# 13448_ATMEGA328_prog.net
KiCad netlist of a schematic drawn in EAGLE
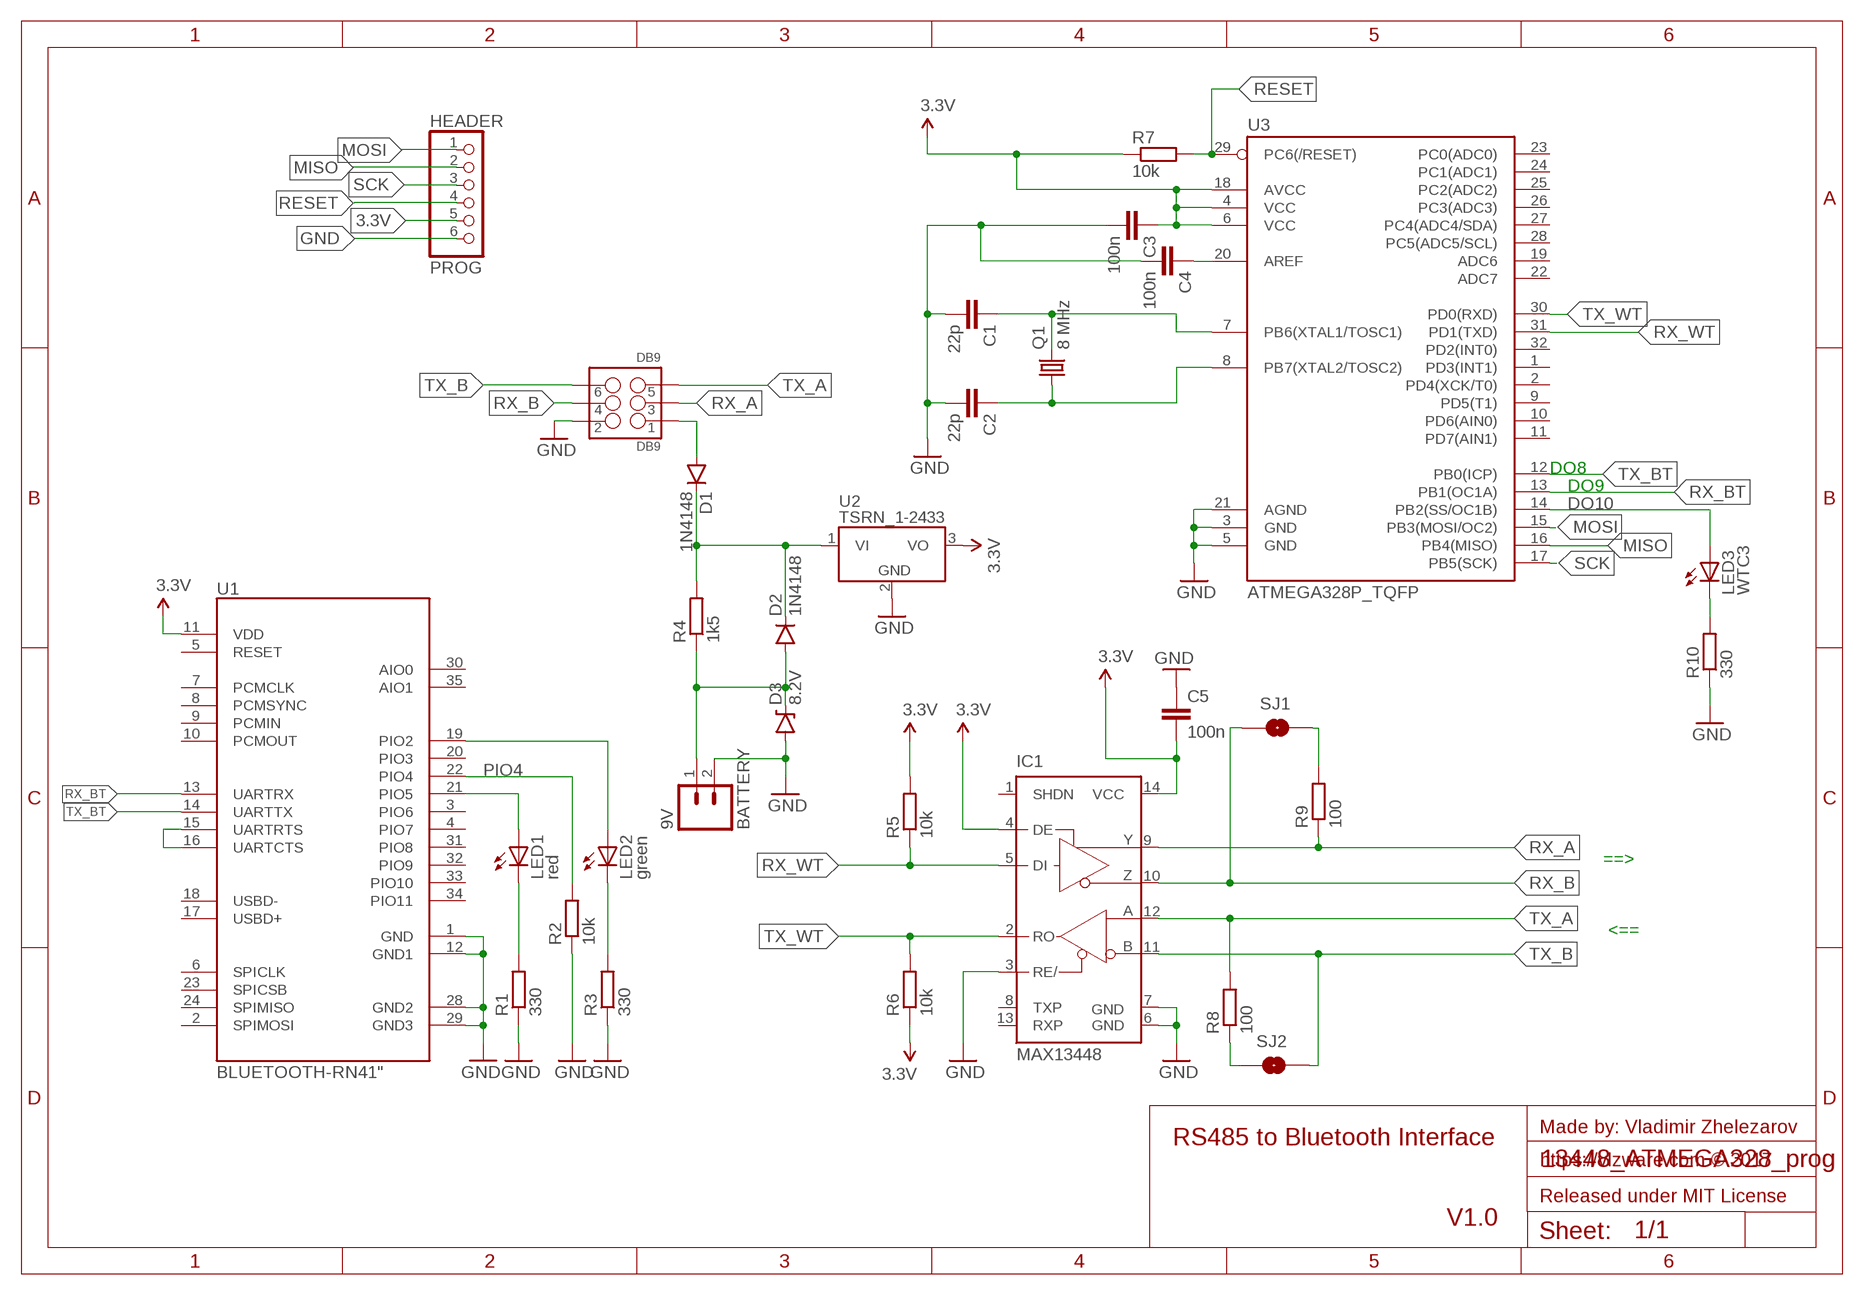
[diagram p0: schematic, sheet 1]

(export (version "E")
  (design (tool "Eeschema 10.0.6"))
  (components
    (comp (ref "BATTERY")
      (value "9V")
      (footprint "eagle-import:1X02_LOCK")
      (libsource (lib "eagle-import") (part "M02LOCK"))
    )
    (comp (ref "C1")
      (value "22p")
      (footprint "eagle-import:1206")
      (libsource (lib "eagle-import") (part "CAP1206"))
    )
    (comp (ref "C2")
      (value "22p")
      (footprint "eagle-import:1206")
      (libsource (lib "eagle-import") (part "CAP1206"))
    )
    (comp (ref "C3")
      (value "100n")
      (footprint "eagle-import:1206")
      (libsource (lib "eagle-import") (part "CAP1206"))
    )
    (comp (ref "C4")
      (value "100n")
      (footprint "eagle-import:1206")
      (libsource (lib "eagle-import") (part "CAP1206"))
    )
    (comp (ref "C5")
      (value "100n")
      (footprint "eagle-import:1206")
      (libsource (lib "eagle-import") (part "CAP1206"))
    )
    (comp (ref "D1")
      (value "1N4148")
      (footprint "eagle-import:DIODE-1N4148")
      (libsource (lib "eagle-import") (part "DIODE1N4148"))
    )
    (comp (ref "D2")
      (value "1N4148")
      (footprint "eagle-import:DIODE-1N4148")
      (libsource (lib "eagle-import") (part "DIODE1N4148"))
    )
    (comp (ref "D3")
      (value "8.2V")
      (footprint "eagle-import:DIODE-BZT52")
      (libsource (lib "eagle-import") (part "DIODE-ZENER"))
    )
    (comp (ref "DB9")
      (value "DB9")
      (footprint "eagle-import:2X3")
      (libsource (lib "eagle-import") (part "M03X22X3_SILK_MALE_PTH"))
    )
    (comp (ref "HEADER")
      (value "PROG")
      (footprint "eagle-import:1X06")
      (libsource (lib "eagle-import") (part "PINHD-1X6"))
    )
    (comp (ref "IC1")
      (value "MAX13448")
      (footprint "eagle-import:SO14")
      (fields (field (name "MPN") "MAX3465CSD+"))
      (libsource (lib "eagle-import") (part "MAX346SD5C"))
    )
    (comp (ref "LED1")
      (value "red")
      (footprint "eagle-import:LED3MM")
      (libsource (lib "eagle-import") (part "LED3MM"))
    )
    (comp (ref "LED2")
      (value "green")
      (footprint "eagle-import:LED3MM")
      (libsource (lib "eagle-import") (part "LED3MM"))
    )
    (comp (ref "LED3")
      (value "WTC3")
      (footprint "eagle-import:LED3MM")
      (libsource (lib "eagle-import") (part "LED3MM"))
    )
    (comp (ref "Q1")
      (value "8 MHz")
      (footprint "eagle-import:HC49UP")
      (libsource (lib "eagle-import") (part "CRYSTALHC49UP"))
    )
    (comp (ref "R1")
      (value "330")
      (footprint "eagle-import:M1206")
      (libsource (lib "eagle-import") (part "R-EU_M1206"))
    )
    (comp (ref "R2")
      (value "10k")
      (footprint "eagle-import:M1206")
      (libsource (lib "eagle-import") (part "R-EU_M1206"))
    )
    (comp (ref "R3")
      (value "330")
      (footprint "eagle-import:M1206")
      (libsource (lib "eagle-import") (part "R-EU_M1206"))
    )
    (comp (ref "R4")
      (value "1k5")
      (footprint "eagle-import:0204V")
      (libsource (lib "eagle-import") (part "R-EU_0204/2V"))
    )
    (comp (ref "R5")
      (value "10k")
      (footprint "eagle-import:M1206")
      (libsource (lib "eagle-import") (part "R-EU_M1206"))
    )
    (comp (ref "R6")
      (value "10k")
      (footprint "eagle-import:M1206")
      (libsource (lib "eagle-import") (part "R-EU_M1206"))
    )
    (comp (ref "R7")
      (value "10k")
      (footprint "eagle-import:M1206")
      (libsource (lib "eagle-import") (part "R-EU_M1206"))
    )
    (comp (ref "R8")
      (value "100")
      (footprint "eagle-import:M1206")
      (libsource (lib "eagle-import") (part "R-EU_M1206"))
    )
    (comp (ref "R9")
      (value "100")
      (footprint "eagle-import:M1206")
      (libsource (lib "eagle-import") (part "R-EU_M1206"))
    )
    (comp (ref "R10")
      (value "330")
      (footprint "eagle-import:M1206")
      (libsource (lib "eagle-import") (part "R-EU_M1206"))
    )
    (comp (ref "SJ1")
      (value "SOLDERJUMPERNC")
      (footprint "eagle-import:SJ_2S")
      (libsource (lib "eagle-import") (part "SOLDERJUMPERNC"))
    )
    (comp (ref "SJ2")
      (value "SOLDERJUMPERNC")
      (footprint "eagle-import:SJ_2S")
      (libsource (lib "eagle-import") (part "SOLDERJUMPERNC"))
    )
    (comp (ref "U1")
      (value "BLUETOOTH-RN41\"")
      (footprint "eagle-import:RN41")
      (libsource (lib "eagle-import") (part "BLUETOOTH-RN41{dblquote}"))
    )
    (comp (ref "U2")
      (value "TSRN_1-2433")
      (footprint "eagle-import:TSR-1")
      (libsource (lib "eagle-import") (part "TSR_1-2450"))
    )
    (comp (ref "U3")
      (value "ATMEGA328P_TQFP")
      (footprint "eagle-import:TQFP32-08")
      (libsource (lib "eagle-import") (part "ATMEGA328P_TQFP"))
    )
  )
  (nets
    (net (code "1") (name "/DO10") (class "Default")
      (node (ref "LED3") (pin "A") (pinfunction "A_A") (pintype "passive"))
      (node (ref "U3") (pin "14") (pinfunction "PB2(SS/OC1B)_14") (pintype "bidirectional"))
    )
    (net (code "2") (name "/PIO4") (class "Default")
      (node (ref "R2") (pin "2") (pinfunction "2_2") (pintype "passive"))
      (node (ref "U1") (pin "22") (pinfunction "PIO4_22") (pintype "bidirectional"))
    )
    (net (code "3") (name "3.3V") (class "Default")
      (node (ref "C3") (pin "1") (pinfunction "1_1") (pintype "passive"))
      (node (ref "C5") (pin "2") (pinfunction "2_2") (pintype "passive"))
      (node (ref "HEADER") (pin "5") (pinfunction "5_5") (pintype "passive"))
      (node (ref "IC1") (pin "14") (pinfunction "VCC_14") (pintype "power_in"))
      (node (ref "IC1") (pin "4") (pinfunction "DE_4") (pintype "input"))
      (node (ref "R5") (pin "2") (pinfunction "2_2") (pintype "passive"))
      (node (ref "R6") (pin "1") (pinfunction "1_1") (pintype "passive"))
      (node (ref "R7") (pin "1") (pinfunction "1_1") (pintype "passive"))
      (node (ref "U1") (pin "11") (pinfunction "VDD_11") (pintype "bidirectional"))
      (node (ref "U2") (pin "3") (pinfunction "VO_3") (pintype "power_in"))
      (node (ref "U3") (pin "18") (pinfunction "AVCC_18") (pintype "bidirectional"))
      (node (ref "U3") (pin "4") (pinfunction "VCC_4") (pintype "bidirectional"))
      (node (ref "U3") (pin "6") (pinfunction "VCC_6") (pintype "bidirectional"))
    )
    (net (code "4") (name "GND") (class "Default")
      (node (ref "BATTERY") (pin "2") (pinfunction "2_2") (pintype "passive"))
      (node (ref "C1") (pin "2") (pinfunction "2_2") (pintype "passive"))
      (node (ref "C2") (pin "2") (pinfunction "2_2") (pintype "passive"))
      (node (ref "C3") (pin "2") (pinfunction "2_2") (pintype "passive"))
      (node (ref "C4") (pin "2") (pinfunction "2_2") (pintype "passive"))
      (node (ref "C5") (pin "1") (pinfunction "1_1") (pintype "passive"))
      (node (ref "D3") (pin "A") (pinfunction "A_A") (pintype "passive"))
      (node (ref "DB9") (pin "2") (pinfunction "2_2") (pintype "bidirectional"))
      (node (ref "HEADER") (pin "6") (pinfunction "6_6") (pintype "passive"))
      (node (ref "IC1") (pin "3") (pinfunction "RE/_3") (pintype "input"))
      (node (ref "IC1") (pin "6") (pinfunction "GND_6") (pintype "power_in"))
      (node (ref "IC1") (pin "7") (pinfunction "GND_7") (pintype "power_in"))
      (node (ref "R1") (pin "1") (pinfunction "1_1") (pintype "passive"))
      (node (ref "R10") (pin "1") (pinfunction "1_1") (pintype "passive"))
      (node (ref "R2") (pin "1") (pinfunction "1_1") (pintype "passive"))
      (node (ref "R3") (pin "1") (pinfunction "1_1") (pintype "passive"))
      (node (ref "U1") (pin "1") (pinfunction "GND_1") (pintype "bidirectional"))
      (node (ref "U1") (pin "12") (pinfunction "GND1_12") (pintype "bidirectional"))
      (node (ref "U1") (pin "28") (pinfunction "GND2_28") (pintype "bidirectional"))
      (node (ref "U1") (pin "29") (pinfunction "GND3_29") (pintype "bidirectional"))
      (node (ref "U2") (pin "2") (pinfunction "GND_2") (pintype "power_in"))
      (node (ref "U3") (pin "21") (pinfunction "AGND_21") (pintype "bidirectional"))
      (node (ref "U3") (pin "3") (pinfunction "GND_3") (pintype "bidirectional"))
      (node (ref "U3") (pin "5") (pinfunction "GND_5") (pintype "bidirectional"))
    )
    (net (code "5") (name "MISO") (class "Default")
      (node (ref "HEADER") (pin "2") (pinfunction "2_2") (pintype "passive"))
      (node (ref "U3") (pin "16") (pinfunction "PB4(MISO)_16") (pintype "bidirectional"))
    )
    (net (code "6") (name "MOSI") (class "Default")
      (node (ref "HEADER") (pin "1") (pinfunction "1_1") (pintype "passive"))
      (node (ref "U3") (pin "15") (pinfunction "PB3(MOSI/OC2)_15") (pintype "bidirectional"))
    )
    (net (code "7") (name "Net-(BATTERY-Pad1)") (class "Default")
      (node (ref "BATTERY") (pin "1") (pinfunction "1_1") (pintype "passive"))
      (node (ref "D2") (pin "A") (pinfunction "A_A") (pintype "passive"))
      (node (ref "D3") (pin "C") (pinfunction "C_C") (pintype "passive"))
      (node (ref "R4") (pin "1") (pinfunction "1_1") (pintype "passive"))
    )
    (net (code "8") (name "Net-(D1-PadA)") (class "Default")
      (node (ref "D1") (pin "A") (pinfunction "A_A") (pintype "passive"))
      (node (ref "DB9") (pin "1") (pinfunction "1_1") (pintype "bidirectional"))
    )
    (net (code "9") (name "Net-(LED1-C)") (class "Default")
      (node (ref "LED1") (pin "K") (pinfunction "C_K") (pintype "passive"))
      (node (ref "R1") (pin "2") (pinfunction "2_2") (pintype "passive"))
    )
    (net (code "10") (name "Net-(LED2-C)") (class "Default")
      (node (ref "LED2") (pin "K") (pinfunction "C_K") (pintype "passive"))
      (node (ref "R3") (pin "2") (pinfunction "2_2") (pintype "passive"))
    )
    (net (code "11") (name "Net-(LED3-C)") (class "Default")
      (node (ref "LED3") (pin "K") (pinfunction "C_K") (pintype "passive"))
      (node (ref "R10") (pin "2") (pinfunction "2_2") (pintype "passive"))
    )
    (net (code "12") (name "Net-(R8-Pad1)") (class "Default")
      (node (ref "R8") (pin "1") (pinfunction "1_1") (pintype "passive"))
      (node (ref "SJ2") (pin "1") (pinfunction "1_1") (pintype "passive"))
    )
    (net (code "13") (name "Net-(R9-Pad2)") (class "Default")
      (node (ref "R9") (pin "2") (pinfunction "2_2") (pintype "passive"))
      (node (ref "SJ1") (pin "2") (pinfunction "2_2") (pintype "passive"))
    )
    (net (code "14") (name "Net-(U1-PIO2)") (class "Default")
      (node (ref "LED2") (pin "A") (pinfunction "A_A") (pintype "passive"))
      (node (ref "U1") (pin "19") (pinfunction "PIO2_19") (pintype "bidirectional"))
    )
    (net (code "15") (name "Net-(U1-PIO5)") (class "Default")
      (node (ref "LED1") (pin "A") (pinfunction "A_A") (pintype "passive"))
      (node (ref "U1") (pin "21") (pinfunction "PIO5_21") (pintype "bidirectional"))
    )
    (net (code "16") (name "Net-(U1-UARTCTS)") (class "Default")
      (node (ref "U1") (pin "15") (pinfunction "UARTRTS_15") (pintype "bidirectional"))
      (node (ref "U1") (pin "16") (pinfunction "UARTCTS_16") (pintype "bidirectional"))
    )
    (net (code "17") (name "Net-(U2-VI)") (class "Default")
      (node (ref "D1") (pin "C") (pinfunction "C_C") (pintype "passive"))
      (node (ref "D2") (pin "C") (pinfunction "C_C") (pintype "passive"))
      (node (ref "R4") (pin "2") (pinfunction "2_2") (pintype "passive"))
      (node (ref "U2") (pin "1") (pinfunction "VI_1") (pintype "power_in"))
    )
    (net (code "18") (name "Net-(U3-AREF)") (class "Default")
      (node (ref "C4") (pin "1") (pinfunction "1_1") (pintype "passive"))
      (node (ref "U3") (pin "20") (pinfunction "AREF_20") (pintype "bidirectional"))
    )
    (net (code "19") (name "Net-(U3-PB6(XTAL1{slash}TOSC1))") (class "Default")
      (node (ref "C1") (pin "1") (pinfunction "1_1") (pintype "passive"))
      (node (ref "Q1") (pin "2") (pinfunction "2_2") (pintype "passive"))
      (node (ref "U3") (pin "7") (pinfunction "PB6(XTAL1/TOSC1)_7") (pintype "bidirectional"))
    )
    (net (code "20") (name "Net-(U3-PB7(XTAL2{slash}TOSC2))") (class "Default")
      (node (ref "C2") (pin "1") (pinfunction "1_1") (pintype "passive"))
      (node (ref "Q1") (pin "1") (pinfunction "1_1") (pintype "passive"))
      (node (ref "U3") (pin "8") (pinfunction "PB7(XTAL2/TOSC2)_8") (pintype "bidirectional"))
    )
    (net (code "21") (name "RESET") (class "Default")
      (node (ref "HEADER") (pin "4") (pinfunction "4_4") (pintype "passive"))
      (node (ref "R7") (pin "2") (pinfunction "2_2") (pintype "passive"))
      (node (ref "U3") (pin "29") (pinfunction "PC6(/RESET)_29") (pintype "bidirectional"))
    )
    (net (code "22") (name "RX_A") (class "Default")
      (node (ref "DB9") (pin "3") (pinfunction "3_3") (pintype "bidirectional"))
      (node (ref "IC1") (pin "9") (pinfunction "Y_9") (pintype "output"))
      (node (ref "R9") (pin "1") (pinfunction "1_1") (pintype "passive"))
    )
    (net (code "23") (name "RX_B") (class "Default")
      (node (ref "DB9") (pin "4") (pinfunction "4_4") (pintype "bidirectional"))
      (node (ref "IC1") (pin "10") (pinfunction "Z_10") (pintype "output"))
      (node (ref "SJ1") (pin "1") (pinfunction "1_1") (pintype "passive"))
    )
    (net (code "24") (name "RX_BT") (class "Default")
      (node (ref "U1") (pin "13") (pinfunction "UARTRX_13") (pintype "bidirectional"))
      (node (ref "U3") (pin "13") (pinfunction "PB1(OC1A)_13") (pintype "bidirectional"))
    )
    (net (code "25") (name "RX_WT") (class "Default")
      (node (ref "IC1") (pin "5") (pinfunction "DI_5") (pintype "input"))
      (node (ref "R5") (pin "1") (pinfunction "1_1") (pintype "passive"))
      (node (ref "U3") (pin "31") (pinfunction "PD1(TXD)_31") (pintype "bidirectional"))
    )
    (net (code "26") (name "SCK") (class "Default")
      (node (ref "HEADER") (pin "3") (pinfunction "3_3") (pintype "passive"))
      (node (ref "U3") (pin "17") (pinfunction "PB5(SCK)_17") (pintype "bidirectional"))
    )
    (net (code "27") (name "TX_A") (class "Default")
      (node (ref "DB9") (pin "5") (pinfunction "5_5") (pintype "bidirectional"))
      (node (ref "IC1") (pin "12") (pinfunction "A_12") (pintype "input"))
      (node (ref "R8") (pin "2") (pinfunction "2_2") (pintype "passive"))
    )
    (net (code "28") (name "TX_B") (class "Default")
      (node (ref "DB9") (pin "6") (pinfunction "6_6") (pintype "bidirectional"))
      (node (ref "IC1") (pin "11") (pinfunction "B_11") (pintype "input"))
      (node (ref "SJ2") (pin "2") (pinfunction "2_2") (pintype "passive"))
    )
    (net (code "29") (name "TX_BT") (class "Default")
      (node (ref "U1") (pin "14") (pinfunction "UARTTX_14") (pintype "bidirectional"))
      (node (ref "U3") (pin "12") (pinfunction "PB0(ICP)_12") (pintype "bidirectional"))
    )
    (net (code "30") (name "TX_WT") (class "Default")
      (node (ref "IC1") (pin "2") (pinfunction "RO_2") (pintype "output"))
      (node (ref "R6") (pin "2") (pinfunction "2_2") (pintype "passive"))
      (node (ref "U3") (pin "30") (pinfunction "PD0(RXD)_30") (pintype "bidirectional"))
    )
    (net (code "31") (name "unconnected-(IC1-RXP-Pad13)") (class "Default")
      (node (ref "IC1") (pin "13") (pinfunction "RXP_13") (pintype "passive"))
    )
    (net (code "32") (name "unconnected-(IC1-SHDN-Pad1)") (class "Default")
      (node (ref "IC1") (pin "1") (pinfunction "SHDN_1") (pintype "input"))
    )
    (net (code "33") (name "unconnected-(IC1-TXP-Pad8)") (class "Default")
      (node (ref "IC1") (pin "8") (pinfunction "TXP_8") (pintype "passive"))
    )
    (net (code "34") (name "unconnected-(U1-AIO0-Pad30)") (class "Default")
      (node (ref "U1") (pin "30") (pinfunction "AIO0_30") (pintype "bidirectional"))
    )
    (net (code "35") (name "unconnected-(U1-AIO1-Pad35)") (class "Default")
      (node (ref "U1") (pin "35") (pinfunction "AIO1_35") (pintype "bidirectional"))
    )
    (net (code "36") (name "unconnected-(U1-PCMCLK-Pad7)") (class "Default")
      (node (ref "U1") (pin "7") (pinfunction "PCMCLK_7") (pintype "bidirectional"))
    )
    (net (code "37") (name "unconnected-(U1-PCMIN-Pad9)") (class "Default")
      (node (ref "U1") (pin "9") (pinfunction "PCMIN_9") (pintype "bidirectional"))
    )
    (net (code "38") (name "unconnected-(U1-PCMOUT-Pad10)") (class "Default")
      (node (ref "U1") (pin "10") (pinfunction "PCMOUT_10") (pintype "bidirectional"))
    )
    (net (code "39") (name "unconnected-(U1-PCMSYNC-Pad8)") (class "Default")
      (node (ref "U1") (pin "8") (pinfunction "PCMSYNC_8") (pintype "bidirectional"))
    )
    (net (code "40") (name "unconnected-(U1-PIO3-Pad20)") (class "Default")
      (node (ref "U1") (pin "20") (pinfunction "PIO3_20") (pintype "bidirectional"))
    )
    (net (code "41") (name "unconnected-(U1-PIO6-Pad3)") (class "Default")
      (node (ref "U1") (pin "3") (pinfunction "PIO6_3") (pintype "bidirectional"))
    )
    (net (code "42") (name "unconnected-(U1-PIO7-Pad4)") (class "Default")
      (node (ref "U1") (pin "4") (pinfunction "PIO7_4") (pintype "bidirectional"))
    )
    (net (code "43") (name "unconnected-(U1-PIO8-Pad31)") (class "Default")
      (node (ref "U1") (pin "31") (pinfunction "PIO8_31") (pintype "bidirectional"))
    )
    (net (code "44") (name "unconnected-(U1-PIO9-Pad32)") (class "Default")
      (node (ref "U1") (pin "32") (pinfunction "PIO9_32") (pintype "bidirectional"))
    )
    (net (code "45") (name "unconnected-(U1-PIO10-Pad33)") (class "Default")
      (node (ref "U1") (pin "33") (pinfunction "PIO10_33") (pintype "bidirectional"))
    )
    (net (code "46") (name "unconnected-(U1-PIO11-Pad34)") (class "Default")
      (node (ref "U1") (pin "34") (pinfunction "PIO11_34") (pintype "bidirectional"))
    )
    (net (code "47") (name "unconnected-(U1-RESET-Pad5)") (class "Default")
      (node (ref "U1") (pin "5") (pinfunction "RESET_5") (pintype "bidirectional"))
    )
    (net (code "48") (name "unconnected-(U1-SPICLK-Pad6)") (class "Default")
      (node (ref "U1") (pin "6") (pinfunction "SPICLK_6") (pintype "bidirectional"))
    )
    (net (code "49") (name "unconnected-(U1-SPICSB-Pad23)") (class "Default")
      (node (ref "U1") (pin "23") (pinfunction "SPICSB_23") (pintype "bidirectional"))
    )
    (net (code "50") (name "unconnected-(U1-SPIMISO-Pad24)") (class "Default")
      (node (ref "U1") (pin "24") (pinfunction "SPIMISO_24") (pintype "bidirectional"))
    )
    (net (code "51") (name "unconnected-(U1-SPIMOSI-Pad2)") (class "Default")
      (node (ref "U1") (pin "2") (pinfunction "SPIMOSI_2") (pintype "bidirectional"))
    )
    (net (code "52") (name "unconnected-(U1-USBD+-Pad17)") (class "Default")
      (node (ref "U1") (pin "17") (pinfunction "USBD+_17") (pintype "bidirectional"))
    )
    (net (code "53") (name "unconnected-(U1-USBD--Pad18)") (class "Default")
      (node (ref "U1") (pin "18") (pinfunction "USBD-_18") (pintype "bidirectional"))
    )
    (net (code "54") (name "unconnected-(U3-ADC6-Pad19)") (class "Default")
      (node (ref "U3") (pin "19") (pinfunction "ADC6_19") (pintype "bidirectional"))
    )
    (net (code "55") (name "unconnected-(U3-ADC7-Pad22)") (class "Default")
      (node (ref "U3") (pin "22") (pinfunction "ADC7_22") (pintype "bidirectional"))
    )
    (net (code "56") (name "unconnected-(U3-PC0(ADC0)-Pad23)") (class "Default")
      (node (ref "U3") (pin "23") (pinfunction "PC0(ADC0)_23") (pintype "bidirectional"))
    )
    (net (code "57") (name "unconnected-(U3-PC1(ADC1)-Pad24)") (class "Default")
      (node (ref "U3") (pin "24") (pinfunction "PC1(ADC1)_24") (pintype "bidirectional"))
    )
    (net (code "58") (name "unconnected-(U3-PC2(ADC2)-Pad25)") (class "Default")
      (node (ref "U3") (pin "25") (pinfunction "PC2(ADC2)_25") (pintype "bidirectional"))
    )
    (net (code "59") (name "unconnected-(U3-PC3(ADC3)-Pad26)") (class "Default")
      (node (ref "U3") (pin "26") (pinfunction "PC3(ADC3)_26") (pintype "bidirectional"))
    )
    (net (code "60") (name "unconnected-(U3-PC4(ADC4{slash}SDA)-Pad27)") (class "Default")
      (node (ref "U3") (pin "27") (pinfunction "PC4(ADC4/SDA)_27") (pintype "bidirectional"))
    )
    (net (code "61") (name "unconnected-(U3-PC5(ADC5{slash}SCL)-Pad28)") (class "Default")
      (node (ref "U3") (pin "28") (pinfunction "PC5(ADC5/SCL)_28") (pintype "bidirectional"))
    )
    (net (code "62") (name "unconnected-(U3-PD2(INT0)-Pad32)") (class "Default")
      (node (ref "U3") (pin "32") (pinfunction "PD2(INT0)_32") (pintype "bidirectional"))
    )
    (net (code "63") (name "unconnected-(U3-PD3(INT1)-Pad1)") (class "Default")
      (node (ref "U3") (pin "1") (pinfunction "PD3(INT1)_1") (pintype "bidirectional"))
    )
    (net (code "64") (name "unconnected-(U3-PD4(XCK{slash}T0)-Pad2)") (class "Default")
      (node (ref "U3") (pin "2") (pinfunction "PD4(XCK/T0)_2") (pintype "bidirectional"))
    )
    (net (code "65") (name "unconnected-(U3-PD5(T1)-Pad9)") (class "Default")
      (node (ref "U3") (pin "9") (pinfunction "PD5(T1)_9") (pintype "bidirectional"))
    )
    (net (code "66") (name "unconnected-(U3-PD6(AIN0)-Pad10)") (class "Default")
      (node (ref "U3") (pin "10") (pinfunction "PD6(AIN0)_10") (pintype "bidirectional"))
    )
    (net (code "67") (name "unconnected-(U3-PD7(AIN1)-Pad11)") (class "Default")
      (node (ref "U3") (pin "11") (pinfunction "PD7(AIN1)_11") (pintype "bidirectional"))
    )
  )
)
